# SWR_HF.net
KiCad netlist of a schematic drawn in Altium Designer
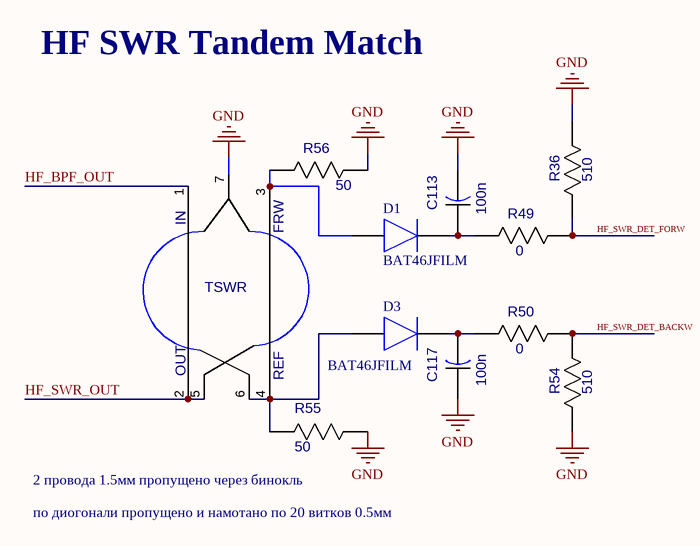
[diagram p0: SWR_HF.SchDoc]

(export (version "E")
  (design (tool "Eeschema 10.0.6"))
  (components
    (comp (ref "C113")
      (value "100n")
      (footprint "CAP_0805")
      (description "CAP_0805")
      (libsource (lib "*") (part "CAP_0805"))
    )
    (comp (ref "C117")
      (value "100n")
      (footprint "CAP_0805")
      (description "CAP_0805")
      (libsource (lib "*") (part "CAP_0805"))
    )
    (comp (ref "D1")
      (value "BAT46JFILM")
      (footprint "SOD2513X117N")
      (description "Diode")
      (fields (field (name "MOUSER PART NUMBER") "511-BAT46JFILM") (field (name "RS PART NUMBER") "7146847P"))
      (libsource (lib "RF-UNIT-BIG_1") (part "BAT46JFILM"))
    )
    (comp (ref "D3")
      (value "BAT46JFILM")
      (footprint "SOD2513X117N")
      (description "Diode")
      (fields (field (name "MOUSER PART NUMBER") "511-BAT46JFILM") (field (name "RS PART NUMBER") "7146847P"))
      (libsource (lib "RF-UNIT-BIG_1") (part "BAT46JFILM"))
    )
    (comp (ref "R36")
      (value "510")
      (footprint "RES_0805")
      (description "RES_0805")
      (libsource (lib "*") (part "RES_0805"))
    )
    (comp (ref "R49")
      (value "0")
      (footprint "RES_0805")
      (description "RES_0805")
      (libsource (lib "*") (part "RES_0805"))
    )
    (comp (ref "R50")
      (value "0")
      (footprint "RES_0805")
      (description "RES_0805")
      (libsource (lib "*") (part "RES_0805"))
    )
    (comp (ref "R54")
      (value "510")
      (footprint "RES_0805")
      (description "RES_0805")
      (libsource (lib "*") (part "RES_0805"))
    )
    (comp (ref "R55")
      (value "50")
      (footprint "RES_1206")
      (description "RES_1206")
      (libsource (lib "*") (part "RES_1206"))
    )
    (comp (ref "R56")
      (value "50")
      (footprint "RES_1206")
      (description "RES_1206")
      (libsource (lib "*") (part "RES_1206"))
    )
    (comp (ref "TSWR")
      (value "SWR_TANDEM_MATCH")
      (footprint "SWR_TANDEM_MATCH")
      (libsource (lib "*") (part "SWR_TANDEM_MATCH"))
    )
  )
  (nets
    (net (code "1") (name "/HF_BPF_OUT") (class "Default")
      (node (ref "TSWR") (pin "1") (pinfunction "1_1") (pintype "passive"))
    )
    (net (code "2") (name "/HF_SWR_DET_BACKW") (class "Default")
      (node (ref "R50") (pin "2") (pinfunction "2_2") (pintype "passive"))
      (node (ref "R54") (pin "2") (pinfunction "2_2") (pintype "passive"))
    )
    (net (code "3") (name "/HF_SWR_DET_FORW") (class "Default")
      (node (ref "R36") (pin "1") (pinfunction "1_1") (pintype "passive"))
      (node (ref "R49") (pin "2") (pinfunction "2_2") (pintype "passive"))
    )
    (net (code "4") (name "/HF_SWR_OUT") (class "Default")
      (node (ref "TSWR") (pin "2") (pinfunction "2_2") (pintype "passive"))
      (node (ref "TSWR") (pin "5") (pinfunction "5_5") (pintype "passive"))
    )
    (net (code "5") (name "GND") (class "Default")
      (node (ref "C113") (pin "2") (pinfunction "2_2") (pintype "passive"))
      (node (ref "C117") (pin "1") (pinfunction "1_1") (pintype "passive"))
      (node (ref "R36") (pin "2") (pinfunction "2_2") (pintype "passive"))
      (node (ref "R54") (pin "1") (pinfunction "1_1") (pintype "passive"))
      (node (ref "R55") (pin "2") (pinfunction "2_2") (pintype "passive"))
      (node (ref "R56") (pin "2") (pinfunction "2_2") (pintype "passive"))
      (node (ref "TSWR") (pin "7") (pinfunction "7_7") (pintype "passive"))
    )
    (net (code "6") (name "Net-(D1-A)") (class "Default")
      (node (ref "D1") (pin "2") (pinfunction "A_2") (pintype "passive"))
      (node (ref "R56") (pin "1") (pinfunction "1_1") (pintype "passive"))
      (node (ref "TSWR") (pin "3") (pinfunction "3_3") (pintype "passive"))
    )
    (net (code "7") (name "Net-(D1-K)") (class "Default")
      (node (ref "C113") (pin "1") (pinfunction "1_1") (pintype "passive"))
      (node (ref "D1") (pin "1") (pinfunction "K_1") (pintype "passive"))
      (node (ref "R49") (pin "1") (pinfunction "1_1") (pintype "passive"))
    )
    (net (code "8") (name "Net-(D3-A)") (class "Default")
      (node (ref "D3") (pin "2") (pinfunction "A_2") (pintype "passive"))
      (node (ref "R55") (pin "1") (pinfunction "1_1") (pintype "passive"))
      (node (ref "TSWR") (pin "4") (pinfunction "4_4") (pintype "passive"))
      (node (ref "TSWR") (pin "6") (pinfunction "6_6") (pintype "passive"))
    )
    (net (code "9") (name "Net-(D3-K)") (class "Default")
      (node (ref "C117") (pin "2") (pinfunction "2_2") (pintype "passive"))
      (node (ref "D3") (pin "1") (pinfunction "K_1") (pintype "passive"))
      (node (ref "R50") (pin "1") (pinfunction "1_1") (pintype "passive"))
    )
  )
)
